# RgbLedPanel.net
KiCad netlist of a schematic drawn in EAGLE
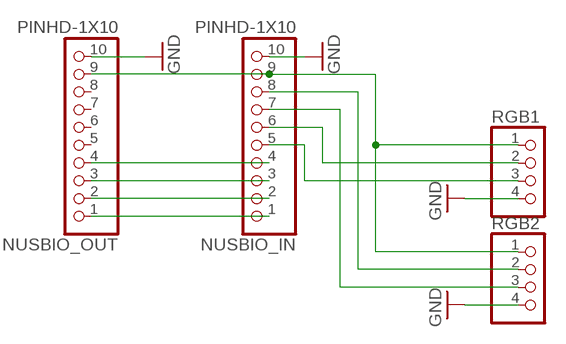
[diagram p0: schematic, sheet 1]

(export (version "E")
  (design (tool "Eeschema 10.0.6"))
  (components
    (comp (ref "NUSBIO_IN")
      (value "PINHD-1X10")
      (footprint "eagle-import:1X10-BIG")
      (libsource (lib "eagle-import") (part "PINHD-1X10"))
    )
    (comp (ref "NUSBIO_OUT")
      (value "PINHD-1X10")
      (footprint "eagle-import:1X10-BIG")
      (libsource (lib "eagle-import") (part "PINHD-1X10"))
    )
    (comp (ref "RGB1")
      (value "PINHD-1X4")
      (footprint "eagle-import:1X04")
      (libsource (lib "eagle-import") (part "PINHD-1X4"))
    )
    (comp (ref "RGB2")
      (value "PINHD-1X4")
      (footprint "eagle-import:1X04")
      (libsource (lib "eagle-import") (part "PINHD-1X4"))
    )
  )
  (nets
    (net (code "1") (name "GND") (class "Default")
      (node (ref "NUSBIO_IN") (pin "10") (pinfunction "10_10") (pintype "passive"))
      (node (ref "NUSBIO_OUT") (pin "10") (pinfunction "10_10") (pintype "passive"))
      (node (ref "RGB1") (pin "4") (pinfunction "4_4") (pintype "passive"))
      (node (ref "RGB2") (pin "4") (pinfunction "4_4") (pintype "passive"))
    )
    (net (code "2") (name "Net-(NUSBIO_IN-Pad1)") (class "Default")
      (node (ref "NUSBIO_IN") (pin "1") (pinfunction "1_1") (pintype "passive"))
      (node (ref "NUSBIO_OUT") (pin "1") (pinfunction "1_1") (pintype "passive"))
    )
    (net (code "3") (name "Net-(NUSBIO_IN-Pad2)") (class "Default")
      (node (ref "NUSBIO_IN") (pin "2") (pinfunction "2_2") (pintype "passive"))
      (node (ref "NUSBIO_OUT") (pin "2") (pinfunction "2_2") (pintype "passive"))
    )
    (net (code "4") (name "Net-(NUSBIO_IN-Pad3)") (class "Default")
      (node (ref "NUSBIO_IN") (pin "3") (pinfunction "3_3") (pintype "passive"))
      (node (ref "NUSBIO_OUT") (pin "3") (pinfunction "3_3") (pintype "passive"))
    )
    (net (code "5") (name "Net-(NUSBIO_IN-Pad4)") (class "Default")
      (node (ref "NUSBIO_IN") (pin "4") (pinfunction "4_4") (pintype "passive"))
      (node (ref "NUSBIO_OUT") (pin "4") (pinfunction "4_4") (pintype "passive"))
    )
    (net (code "6") (name "Net-(NUSBIO_IN-Pad5)") (class "Default")
      (node (ref "NUSBIO_IN") (pin "5") (pinfunction "5_5") (pintype "passive"))
      (node (ref "RGB1") (pin "3") (pinfunction "3_3") (pintype "passive"))
    )
    (net (code "7") (name "Net-(NUSBIO_IN-Pad6)") (class "Default")
      (node (ref "NUSBIO_IN") (pin "6") (pinfunction "6_6") (pintype "passive"))
      (node (ref "RGB1") (pin "2") (pinfunction "2_2") (pintype "passive"))
    )
    (net (code "8") (name "Net-(NUSBIO_IN-Pad7)") (class "Default")
      (node (ref "NUSBIO_IN") (pin "7") (pinfunction "7_7") (pintype "passive"))
      (node (ref "RGB2") (pin "3") (pinfunction "3_3") (pintype "passive"))
    )
    (net (code "9") (name "Net-(NUSBIO_IN-Pad8)") (class "Default")
      (node (ref "NUSBIO_IN") (pin "8") (pinfunction "8_8") (pintype "passive"))
      (node (ref "RGB2") (pin "2") (pinfunction "2_2") (pintype "passive"))
    )
    (net (code "10") (name "Net-(NUSBIO_IN-Pad9)") (class "Default")
      (node (ref "NUSBIO_IN") (pin "9") (pinfunction "9_9") (pintype "passive"))
      (node (ref "NUSBIO_OUT") (pin "9") (pinfunction "9_9") (pintype "passive"))
      (node (ref "RGB1") (pin "1") (pinfunction "1_1") (pintype "passive"))
      (node (ref "RGB2") (pin "1") (pinfunction "1_1") (pintype "passive"))
    )
    (net (code "11") (name "unconnected-(NUSBIO_OUT-Pad5)") (class "Default")
      (node (ref "NUSBIO_OUT") (pin "5") (pinfunction "5_5") (pintype "passive"))
    )
    (net (code "12") (name "unconnected-(NUSBIO_OUT-Pad6)") (class "Default")
      (node (ref "NUSBIO_OUT") (pin "6") (pinfunction "6_6") (pintype "passive"))
    )
    (net (code "13") (name "unconnected-(NUSBIO_OUT-Pad7)") (class "Default")
      (node (ref "NUSBIO_OUT") (pin "7") (pinfunction "7_7") (pintype "passive"))
    )
    (net (code "14") (name "unconnected-(NUSBIO_OUT-Pad8)") (class "Default")
      (node (ref "NUSBIO_OUT") (pin "8") (pinfunction "8_8") (pintype "passive"))
    )
  )
)
